# The_C64_Big_T_Switcher_FITTEST.net
KiCad netlist of a schematic drawn in EAGLE
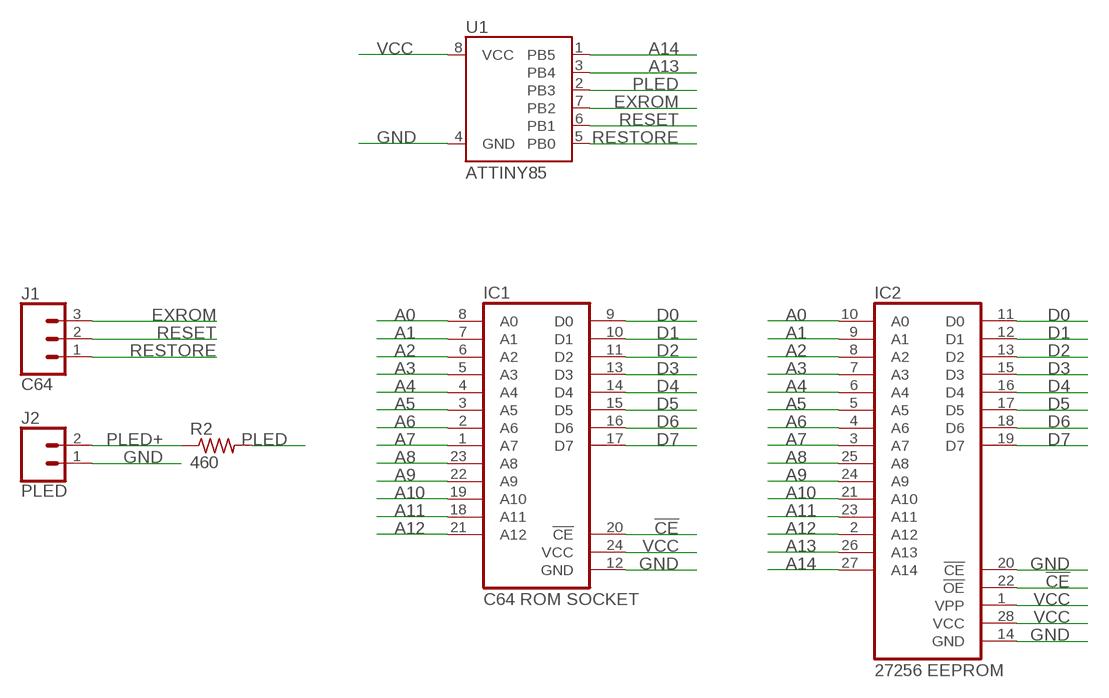
[diagram p0: schematic, sheet 1]

(export (version "E")
  (design (tool "Eeschema 10.0.6"))
  (components
    (comp (ref "IC1")
      (value "C64 ROM SOCKET")
      (footprint "eagle-import:DIL24")
      (libsource (lib "eagle-import") (part "2364"))
    )
    (comp (ref "IC2")
      (value "27256 EEPROM")
      (footprint "eagle-import:DIL28")
      (libsource (lib "eagle-import") (part "27256"))
    )
    (comp (ref "J1")
      (value "C64")
      (footprint "eagle-import:1X03")
      (libsource (lib "eagle-import") (part "CONN_03"))
    )
    (comp (ref "J2")
      (value "PLED")
      (footprint "eagle-import:1X02")
      (libsource (lib "eagle-import") (part "CONN_02"))
    )
    (comp (ref "R2")
      (value "460")
      (footprint "eagle-import:0207_10")
      (libsource (lib "eagle-import") (part "R-US_0207/10"))
    )
    (comp (ref "U1")
      (value "ATTINY85")
      (footprint "eagle-import:ATTINY85")
      (libsource (lib "eagle-import") (part "ATTINY85"))
    )
  )
  (nets
    (net (code "1") (name "/A0") (class "Default")
      (node (ref "IC1") (pin "8") (pinfunction "A0_8") (pintype "bidirectional"))
      (node (ref "IC2") (pin "10") (pinfunction "A0_10") (pintype "bidirectional"))
    )
    (net (code "2") (name "/A1") (class "Default")
      (node (ref "IC1") (pin "7") (pinfunction "A1_7") (pintype "bidirectional"))
      (node (ref "IC2") (pin "9") (pinfunction "A1_9") (pintype "bidirectional"))
    )
    (net (code "3") (name "/A2") (class "Default")
      (node (ref "IC1") (pin "6") (pinfunction "A2_6") (pintype "bidirectional"))
      (node (ref "IC2") (pin "8") (pinfunction "A2_8") (pintype "bidirectional"))
    )
    (net (code "4") (name "/A3") (class "Default")
      (node (ref "IC1") (pin "5") (pinfunction "A3_5") (pintype "bidirectional"))
      (node (ref "IC2") (pin "7") (pinfunction "A3_7") (pintype "bidirectional"))
    )
    (net (code "5") (name "/A4") (class "Default")
      (node (ref "IC1") (pin "4") (pinfunction "A4_4") (pintype "bidirectional"))
      (node (ref "IC2") (pin "6") (pinfunction "A4_6") (pintype "bidirectional"))
    )
    (net (code "6") (name "/A5") (class "Default")
      (node (ref "IC1") (pin "3") (pinfunction "A5_3") (pintype "bidirectional"))
      (node (ref "IC2") (pin "5") (pinfunction "A5_5") (pintype "bidirectional"))
    )
    (net (code "7") (name "/A6") (class "Default")
      (node (ref "IC1") (pin "2") (pinfunction "A6_2") (pintype "bidirectional"))
      (node (ref "IC2") (pin "4") (pinfunction "A6_4") (pintype "bidirectional"))
    )
    (net (code "8") (name "/A7") (class "Default")
      (node (ref "IC1") (pin "1") (pinfunction "A7_1") (pintype "bidirectional"))
      (node (ref "IC2") (pin "3") (pinfunction "A7_3") (pintype "bidirectional"))
    )
    (net (code "9") (name "/A8") (class "Default")
      (node (ref "IC1") (pin "23") (pinfunction "A8_23") (pintype "bidirectional"))
      (node (ref "IC2") (pin "25") (pinfunction "A8_25") (pintype "bidirectional"))
    )
    (net (code "10") (name "/A9") (class "Default")
      (node (ref "IC1") (pin "22") (pinfunction "A9_22") (pintype "bidirectional"))
      (node (ref "IC2") (pin "24") (pinfunction "A9_24") (pintype "bidirectional"))
    )
    (net (code "11") (name "/A10") (class "Default")
      (node (ref "IC1") (pin "19") (pinfunction "A10_19") (pintype "bidirectional"))
      (node (ref "IC2") (pin "21") (pinfunction "A10_21") (pintype "bidirectional"))
    )
    (net (code "12") (name "/A11") (class "Default")
      (node (ref "IC1") (pin "18") (pinfunction "A11_18") (pintype "bidirectional"))
      (node (ref "IC2") (pin "23") (pinfunction "A11_23") (pintype "bidirectional"))
    )
    (net (code "13") (name "/A12") (class "Default")
      (node (ref "IC1") (pin "21") (pinfunction "A12_21") (pintype "bidirectional"))
      (node (ref "IC2") (pin "2") (pinfunction "A12_2") (pintype "bidirectional"))
    )
    (net (code "14") (name "/A13") (class "Default")
      (node (ref "IC2") (pin "26") (pinfunction "A13_26") (pintype "bidirectional"))
      (node (ref "U1") (pin "3") (pinfunction "PB4_3") (pintype "bidirectional"))
    )
    (net (code "15") (name "/A14") (class "Default")
      (node (ref "IC2") (pin "27") (pinfunction "A14_27") (pintype "bidirectional"))
      (node (ref "U1") (pin "1") (pinfunction "PB5_1") (pintype "bidirectional"))
    )
    (net (code "16") (name "/D0") (class "Default")
      (node (ref "IC1") (pin "9") (pinfunction "D0_9") (pintype "bidirectional"))
      (node (ref "IC2") (pin "11") (pinfunction "D0_11") (pintype "bidirectional"))
    )
    (net (code "17") (name "/D1") (class "Default")
      (node (ref "IC1") (pin "10") (pinfunction "D1_10") (pintype "bidirectional"))
      (node (ref "IC2") (pin "12") (pinfunction "D1_12") (pintype "bidirectional"))
    )
    (net (code "18") (name "/D2") (class "Default")
      (node (ref "IC1") (pin "11") (pinfunction "D2_11") (pintype "bidirectional"))
      (node (ref "IC2") (pin "13") (pinfunction "D2_13") (pintype "bidirectional"))
    )
    (net (code "19") (name "/D3") (class "Default")
      (node (ref "IC1") (pin "13") (pinfunction "D3_13") (pintype "bidirectional"))
      (node (ref "IC2") (pin "15") (pinfunction "D3_15") (pintype "bidirectional"))
    )
    (net (code "20") (name "/D4") (class "Default")
      (node (ref "IC1") (pin "14") (pinfunction "D4_14") (pintype "bidirectional"))
      (node (ref "IC2") (pin "16") (pinfunction "D4_16") (pintype "bidirectional"))
    )
    (net (code "21") (name "/D5") (class "Default")
      (node (ref "IC1") (pin "15") (pinfunction "D5_15") (pintype "bidirectional"))
      (node (ref "IC2") (pin "17") (pinfunction "D5_17") (pintype "bidirectional"))
    )
    (net (code "22") (name "/D6") (class "Default")
      (node (ref "IC1") (pin "16") (pinfunction "D6_16") (pintype "bidirectional"))
      (node (ref "IC2") (pin "18") (pinfunction "D6_18") (pintype "bidirectional"))
    )
    (net (code "23") (name "/D7") (class "Default")
      (node (ref "IC1") (pin "17") (pinfunction "D7_17") (pintype "bidirectional"))
      (node (ref "IC2") (pin "19") (pinfunction "D7_19") (pintype "bidirectional"))
    )
    (net (code "24") (name "/EXROM") (class "Default")
      (node (ref "J1") (pin "3") (pinfunction "3_3") (pintype "passive"))
      (node (ref "U1") (pin "7") (pinfunction "PB2_7") (pintype "bidirectional"))
    )
    (net (code "25") (name "/GND") (class "Default")
      (node (ref "IC1") (pin "12") (pinfunction "GND_12") (pintype "power_in"))
      (node (ref "IC2") (pin "14") (pinfunction "GND_14") (pintype "power_in"))
      (node (ref "IC2") (pin "20") (pinfunction "~{CE}_20") (pintype "input"))
      (node (ref "J2") (pin "1") (pinfunction "1_1") (pintype "passive"))
      (node (ref "U1") (pin "4") (pinfunction "GND_4") (pintype "bidirectional"))
    )
    (net (code "26") (name "/PLED") (class "Default")
      (node (ref "R2") (pin "2") (pinfunction "2_2") (pintype "passive"))
      (node (ref "U1") (pin "2") (pinfunction "PB3_2") (pintype "bidirectional"))
    )
    (net (code "27") (name "/PLED+") (class "Default")
      (node (ref "J2") (pin "2") (pinfunction "2_2") (pintype "passive"))
      (node (ref "R2") (pin "1") (pinfunction "1_1") (pintype "passive"))
    )
    (net (code "28") (name "/RESET") (class "Default")
      (node (ref "J1") (pin "2") (pinfunction "2_2") (pintype "passive"))
      (node (ref "U1") (pin "6") (pinfunction "PB1_6") (pintype "bidirectional"))
    )
    (net (code "29") (name "/RESTORE") (class "Default")
      (node (ref "J1") (pin "1") (pinfunction "1_1") (pintype "passive"))
      (node (ref "U1") (pin "5") (pinfunction "PB0_5") (pintype "bidirectional"))
    )
    (net (code "30") (name "/VCC") (class "Default")
      (node (ref "IC1") (pin "24") (pinfunction "VCC_24") (pintype "power_in"))
      (node (ref "IC2") (pin "1") (pinfunction "VPP_1") (pintype "power_in"))
      (node (ref "IC2") (pin "28") (pinfunction "VCC_28") (pintype "power_in"))
      (node (ref "U1") (pin "8") (pinfunction "VCC_8") (pintype "bidirectional"))
    )
    (net (code "31") (name "/~{CE}") (class "Default")
      (node (ref "IC1") (pin "20") (pinfunction "~{CE}_20") (pintype "input"))
      (node (ref "IC2") (pin "22") (pinfunction "~{OE}_22") (pintype "output"))
    )
  )
)
